# SCH_fall_detection_2025-05-21.net
KiCad netlist of a schematic drawn in EasyEDA
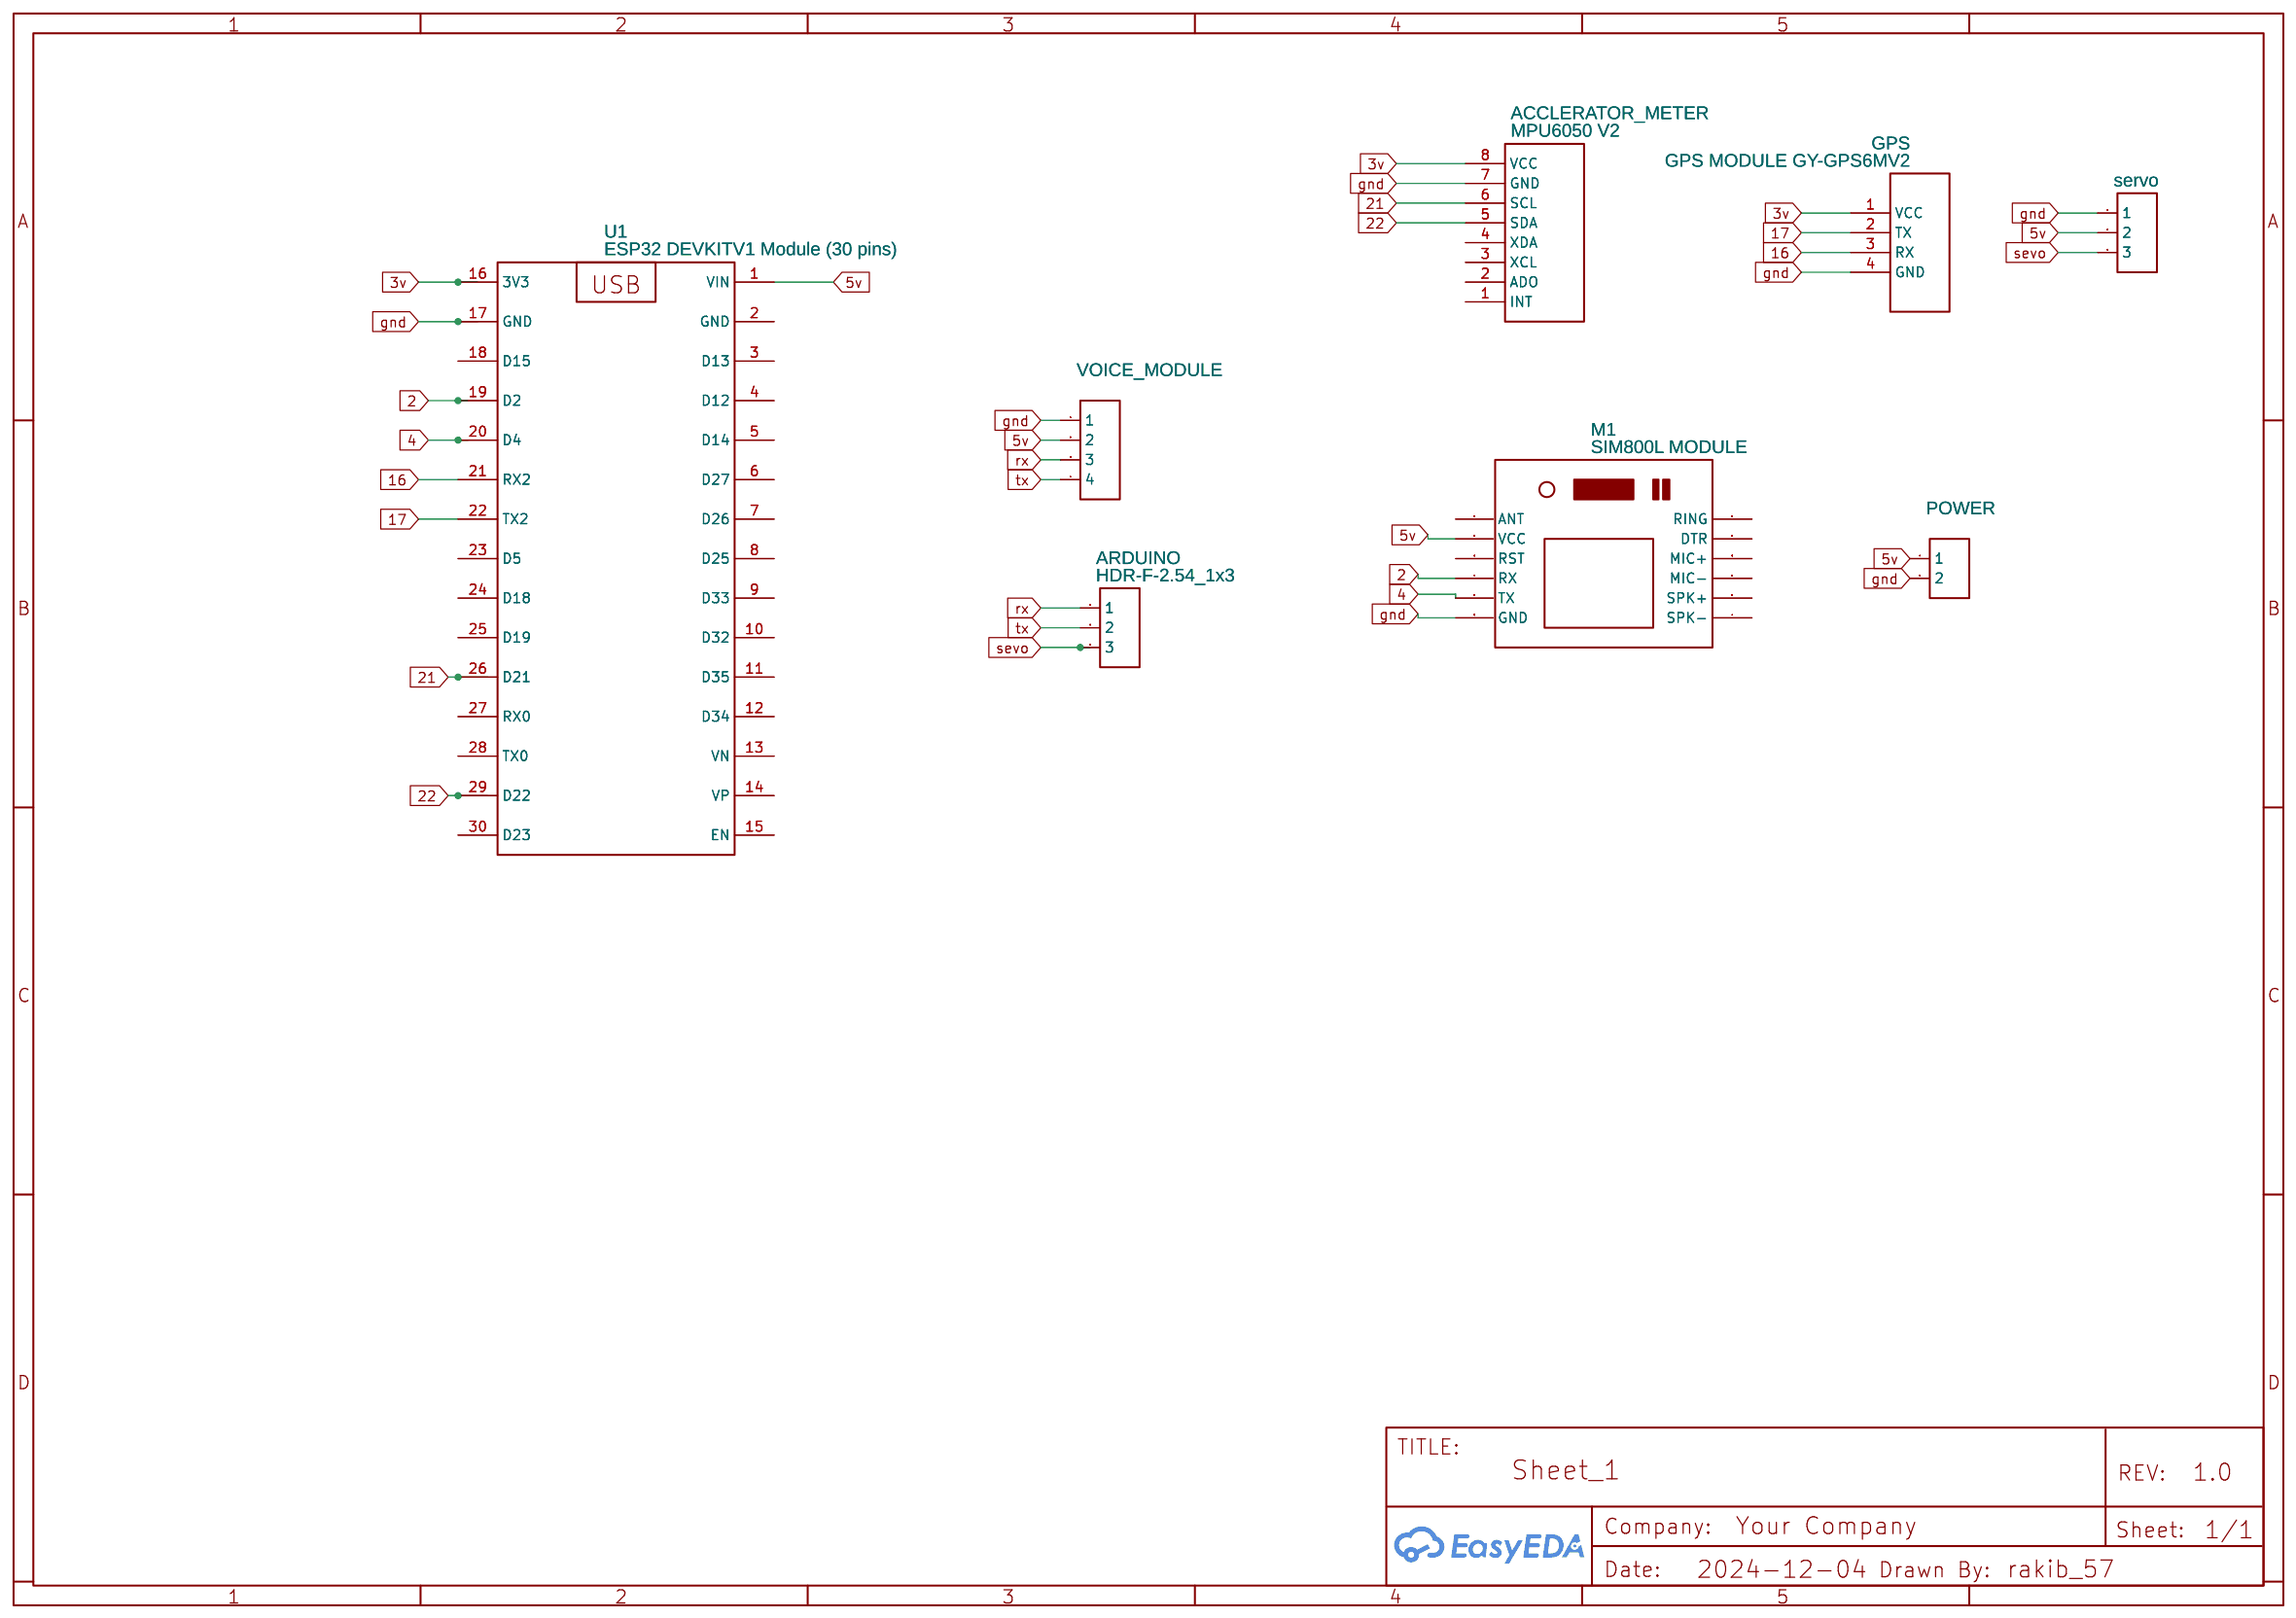
[diagram p0: schematic sheet]

(export (version "E")
  (design (tool "Eeschema 10.0.6"))
  (components
    (comp (ref "ACCLERATOR_METER") (value "MPU6050 V2") (libsource (lib "") (part "MPU6050 V2")))
    (comp (ref "ARDUINO") (value "HDR-F-2.54_1x3") (libsource (lib "") (part "HDR-F-2.54_1x3_1")))
    (comp (ref "GPS") (value "GPS MODULE GY-GPS6MV2") (libsource (lib "") (part "GPS MODULE GY-GPS6MV2")))
    (comp (ref "M1") (value "SIM800L MODULE") (libsource (lib "") (part "SIM800L MODULE COPY")))
    (comp (ref "POWER") (value "HDR-F-2.54_1x2") (libsource (lib "") (part "HDR-F-2.54_1x2")))
    (comp (ref "SERVO") (value "servo") (libsource (lib "") (part "HDR-F-2.54_1x3")))
    (comp (ref "U1")
      (value "ESP32 DEVKITV1 Module (30 pins)")
      (libsource (lib "") (part "ESP32 DEVKITV1 Module (30 pins)"))
    )
    (comp (ref "VOICE_MODULE") (value "HDR-F-2.54_1x4") (libsource (lib "") (part "HDR-F-2.54_1x4")))
  )
  (nets
    (net (code "1") (name "2") (class "Default")
      (node (ref "M1") (pin "4") (pinfunction "RX_4") (pintype "unspecified"))
      (node (ref "U1") (pin "19") (pinfunction "D2_19") (pintype "unspecified"))
    )
    (net (code "2") (name "3v") (class "Default")
      (node (ref "ACCLERATOR_METER") (pin "8") (pinfunction "VCC_8") (pintype "unspecified"))
      (node (ref "GPS") (pin "1") (pinfunction "VCC_1") (pintype "unspecified"))
      (node (ref "U1") (pin "16") (pinfunction "3V3_16") (pintype "unspecified"))
    )
    (net (code "3") (name "4") (class "Default")
      (node (ref "M1") (pin "5") (pinfunction "TX_5") (pintype "unspecified"))
      (node (ref "U1") (pin "20") (pinfunction "D4_20") (pintype "unspecified"))
    )
    (net (code "4") (name "5v") (class "Default")
      (node (ref "M1") (pin "2") (pinfunction "VCC_2") (pintype "unspecified"))
      (node (ref "POWER") (pin "1") (pinfunction "1_1") (pintype "input"))
      (node (ref "SERVO") (pin "2") (pinfunction "2_2") (pintype "input"))
      (node (ref "U1") (pin "1") (pinfunction "VIN_1") (pintype "unspecified"))
      (node (ref "VOICE_MODULE") (pin "2") (pinfunction "2_2") (pintype "unspecified"))
    )
    (net (code "5") (name "16") (class "Default")
      (node (ref "GPS") (pin "3") (pinfunction "RX_3") (pintype "unspecified"))
      (node (ref "U1") (pin "21") (pinfunction "RX2_21") (pintype "unspecified"))
    )
    (net (code "6") (name "17") (class "Default")
      (node (ref "GPS") (pin "2") (pinfunction "TX_2") (pintype "unspecified"))
      (node (ref "U1") (pin "22") (pinfunction "TX2_22") (pintype "unspecified"))
    )
    (net (code "7") (name "21") (class "Default")
      (node (ref "ACCLERATOR_METER") (pin "6") (pinfunction "SCL_6") (pintype "unspecified"))
      (node (ref "U1") (pin "26") (pinfunction "D21_26") (pintype "unspecified"))
    )
    (net (code "8") (name "22") (class "Default")
      (node (ref "ACCLERATOR_METER") (pin "5") (pinfunction "SDA_5") (pintype "unspecified"))
      (node (ref "U1") (pin "29") (pinfunction "D22_29") (pintype "unspecified"))
    )
    (net (code "9") (name "gnd") (class "Default")
      (node (ref "ACCLERATOR_METER") (pin "7") (pinfunction "GND_7") (pintype "unspecified"))
      (node (ref "GPS") (pin "4") (pinfunction "GND_4") (pintype "unspecified"))
      (node (ref "M1") (pin "6") (pinfunction "GND_6") (pintype "unspecified"))
      (node (ref "POWER") (pin "2") (pinfunction "2_2") (pintype "input"))
      (node (ref "SERVO") (pin "1") (pinfunction "1_1") (pintype "input"))
      (node (ref "U1") (pin "17") (pinfunction "GND_17") (pintype "unspecified"))
      (node (ref "VOICE_MODULE") (pin "1") (pinfunction "1_1") (pintype "unspecified"))
    )
    (net (code "10") (name "rx") (class "Default")
      (node (ref "ARDUINO") (pin "1") (pinfunction "1_1") (pintype "input"))
      (node (ref "VOICE_MODULE") (pin "3") (pinfunction "3_3") (pintype "unspecified"))
    )
    (net (code "11") (name "sevo") (class "Default")
      (node (ref "ARDUINO") (pin "3") (pinfunction "3_3") (pintype "input"))
      (node (ref "SERVO") (pin "3") (pinfunction "3_3") (pintype "input"))
    )
    (net (code "12") (name "tx") (class "Default")
      (node (ref "ARDUINO") (pin "2") (pinfunction "2_2") (pintype "input"))
      (node (ref "VOICE_MODULE") (pin "4") (pinfunction "4_4") (pintype "unspecified"))
    )
    (net (code "13") (name "unconnected-(ACCLERATOR_METER-ADO-Pad2)") (class "Default")
      (node (ref "ACCLERATOR_METER") (pin "2") (pinfunction "ADO_2") (pintype "unspecified"))
    )
    (net (code "14") (name "unconnected-(ACCLERATOR_METER-INT-Pad1)") (class "Default")
      (node (ref "ACCLERATOR_METER") (pin "1") (pinfunction "INT_1") (pintype "unspecified"))
    )
    (net (code "15") (name "unconnected-(ACCLERATOR_METER-XCL-Pad3)") (class "Default")
      (node (ref "ACCLERATOR_METER") (pin "3") (pinfunction "XCL_3") (pintype "unspecified"))
    )
    (net (code "16") (name "unconnected-(ACCLERATOR_METER-XDA-Pad4)") (class "Default")
      (node (ref "ACCLERATOR_METER") (pin "4") (pinfunction "XDA_4") (pintype "unspecified"))
    )
    (net (code "17") (name "unconnected-(M1-ANT-Pad1)") (class "Default")
      (node (ref "M1") (pin "1") (pinfunction "ANT_1") (pintype "unspecified"))
    )
    (net (code "18") (name "unconnected-(M1-DTR-Pad11)") (class "Default")
      (node (ref "M1") (pin "11") (pinfunction "DTR_11") (pintype "unspecified"))
    )
    (net (code "19") (name "unconnected-(M1-MIC+-Pad10)") (class "Default")
      (node (ref "M1") (pin "10") (pinfunction "MIC+_10") (pintype "unspecified"))
    )
    (net (code "20") (name "unconnected-(M1-MIC--Pad9)") (class "Default")
      (node (ref "M1") (pin "9") (pinfunction "MIC-_9") (pintype "unspecified"))
    )
    (net (code "21") (name "unconnected-(M1-RING-Pad12)") (class "Default")
      (node (ref "M1") (pin "12") (pinfunction "RING_12") (pintype "unspecified"))
    )
    (net (code "22") (name "unconnected-(M1-RST-Pad3)") (class "Default")
      (node (ref "M1") (pin "3") (pinfunction "RST_3") (pintype "unspecified"))
    )
    (net (code "23") (name "unconnected-(M1-SPK+-Pad8)") (class "Default")
      (node (ref "M1") (pin "8") (pinfunction "SPK+_8") (pintype "unspecified"))
    )
    (net (code "24") (name "unconnected-(M1-SPK--Pad7)") (class "Default")
      (node (ref "M1") (pin "7") (pinfunction "SPK-_7") (pintype "unspecified"))
    )
    (net (code "25") (name "unconnected-(U1-D5-Pad23)") (class "Default")
      (node (ref "U1") (pin "23") (pinfunction "D5_23") (pintype "unspecified"))
    )
    (net (code "26") (name "unconnected-(U1-D12-Pad4)") (class "Default")
      (node (ref "U1") (pin "4") (pinfunction "D12_4") (pintype "unspecified"))
    )
    (net (code "27") (name "unconnected-(U1-D13-Pad3)") (class "Default")
      (node (ref "U1") (pin "3") (pinfunction "D13_3") (pintype "unspecified"))
    )
    (net (code "28") (name "unconnected-(U1-D14-Pad5)") (class "Default")
      (node (ref "U1") (pin "5") (pinfunction "D14_5") (pintype "unspecified"))
    )
    (net (code "29") (name "unconnected-(U1-D15-Pad18)") (class "Default")
      (node (ref "U1") (pin "18") (pinfunction "D15_18") (pintype "unspecified"))
    )
    (net (code "30") (name "unconnected-(U1-D18-Pad24)") (class "Default")
      (node (ref "U1") (pin "24") (pinfunction "D18_24") (pintype "unspecified"))
    )
    (net (code "31") (name "unconnected-(U1-D19-Pad25)") (class "Default")
      (node (ref "U1") (pin "25") (pinfunction "D19_25") (pintype "unspecified"))
    )
    (net (code "32") (name "unconnected-(U1-D23-Pad30)") (class "Default")
      (node (ref "U1") (pin "30") (pinfunction "D23_30") (pintype "unspecified"))
    )
    (net (code "33") (name "unconnected-(U1-D25-Pad8)") (class "Default")
      (node (ref "U1") (pin "8") (pinfunction "D25_8") (pintype "unspecified"))
    )
    (net (code "34") (name "unconnected-(U1-D26-Pad7)") (class "Default")
      (node (ref "U1") (pin "7") (pinfunction "D26_7") (pintype "unspecified"))
    )
    (net (code "35") (name "unconnected-(U1-D27-Pad6)") (class "Default")
      (node (ref "U1") (pin "6") (pinfunction "D27_6") (pintype "unspecified"))
    )
    (net (code "36") (name "unconnected-(U1-D32-Pad10)") (class "Default")
      (node (ref "U1") (pin "10") (pinfunction "D32_10") (pintype "unspecified"))
    )
    (net (code "37") (name "unconnected-(U1-D33-Pad9)") (class "Default")
      (node (ref "U1") (pin "9") (pinfunction "D33_9") (pintype "unspecified"))
    )
    (net (code "38") (name "unconnected-(U1-D34-Pad12)") (class "Default")
      (node (ref "U1") (pin "12") (pinfunction "D34_12") (pintype "unspecified"))
    )
    (net (code "39") (name "unconnected-(U1-D35-Pad11)") (class "Default")
      (node (ref "U1") (pin "11") (pinfunction "D35_11") (pintype "unspecified"))
    )
    (net (code "40") (name "unconnected-(U1-EN-Pad15)") (class "Default")
      (node (ref "U1") (pin "15") (pinfunction "EN_15") (pintype "unspecified"))
    )
    (net (code "41") (name "unconnected-(U1-GND-Pad2)") (class "Default")
      (node (ref "U1") (pin "2") (pinfunction "GND_2") (pintype "unspecified"))
    )
    (net (code "42") (name "unconnected-(U1-RX0-Pad27)") (class "Default")
      (node (ref "U1") (pin "27") (pinfunction "RX0_27") (pintype "unspecified"))
    )
    (net (code "43") (name "unconnected-(U1-TX0-Pad28)") (class "Default")
      (node (ref "U1") (pin "28") (pinfunction "TX0_28") (pintype "unspecified"))
    )
    (net (code "44") (name "unconnected-(U1-VN-Pad13)") (class "Default")
      (node (ref "U1") (pin "13") (pinfunction "VN_13") (pintype "unspecified"))
    )
    (net (code "45") (name "unconnected-(U1-VP-Pad14)") (class "Default")
      (node (ref "U1") (pin "14") (pinfunction "VP_14") (pintype "unspecified"))
    )
  )
)
